# LD_driver.net
KiCad netlist of a schematic drawn in Altium Designer
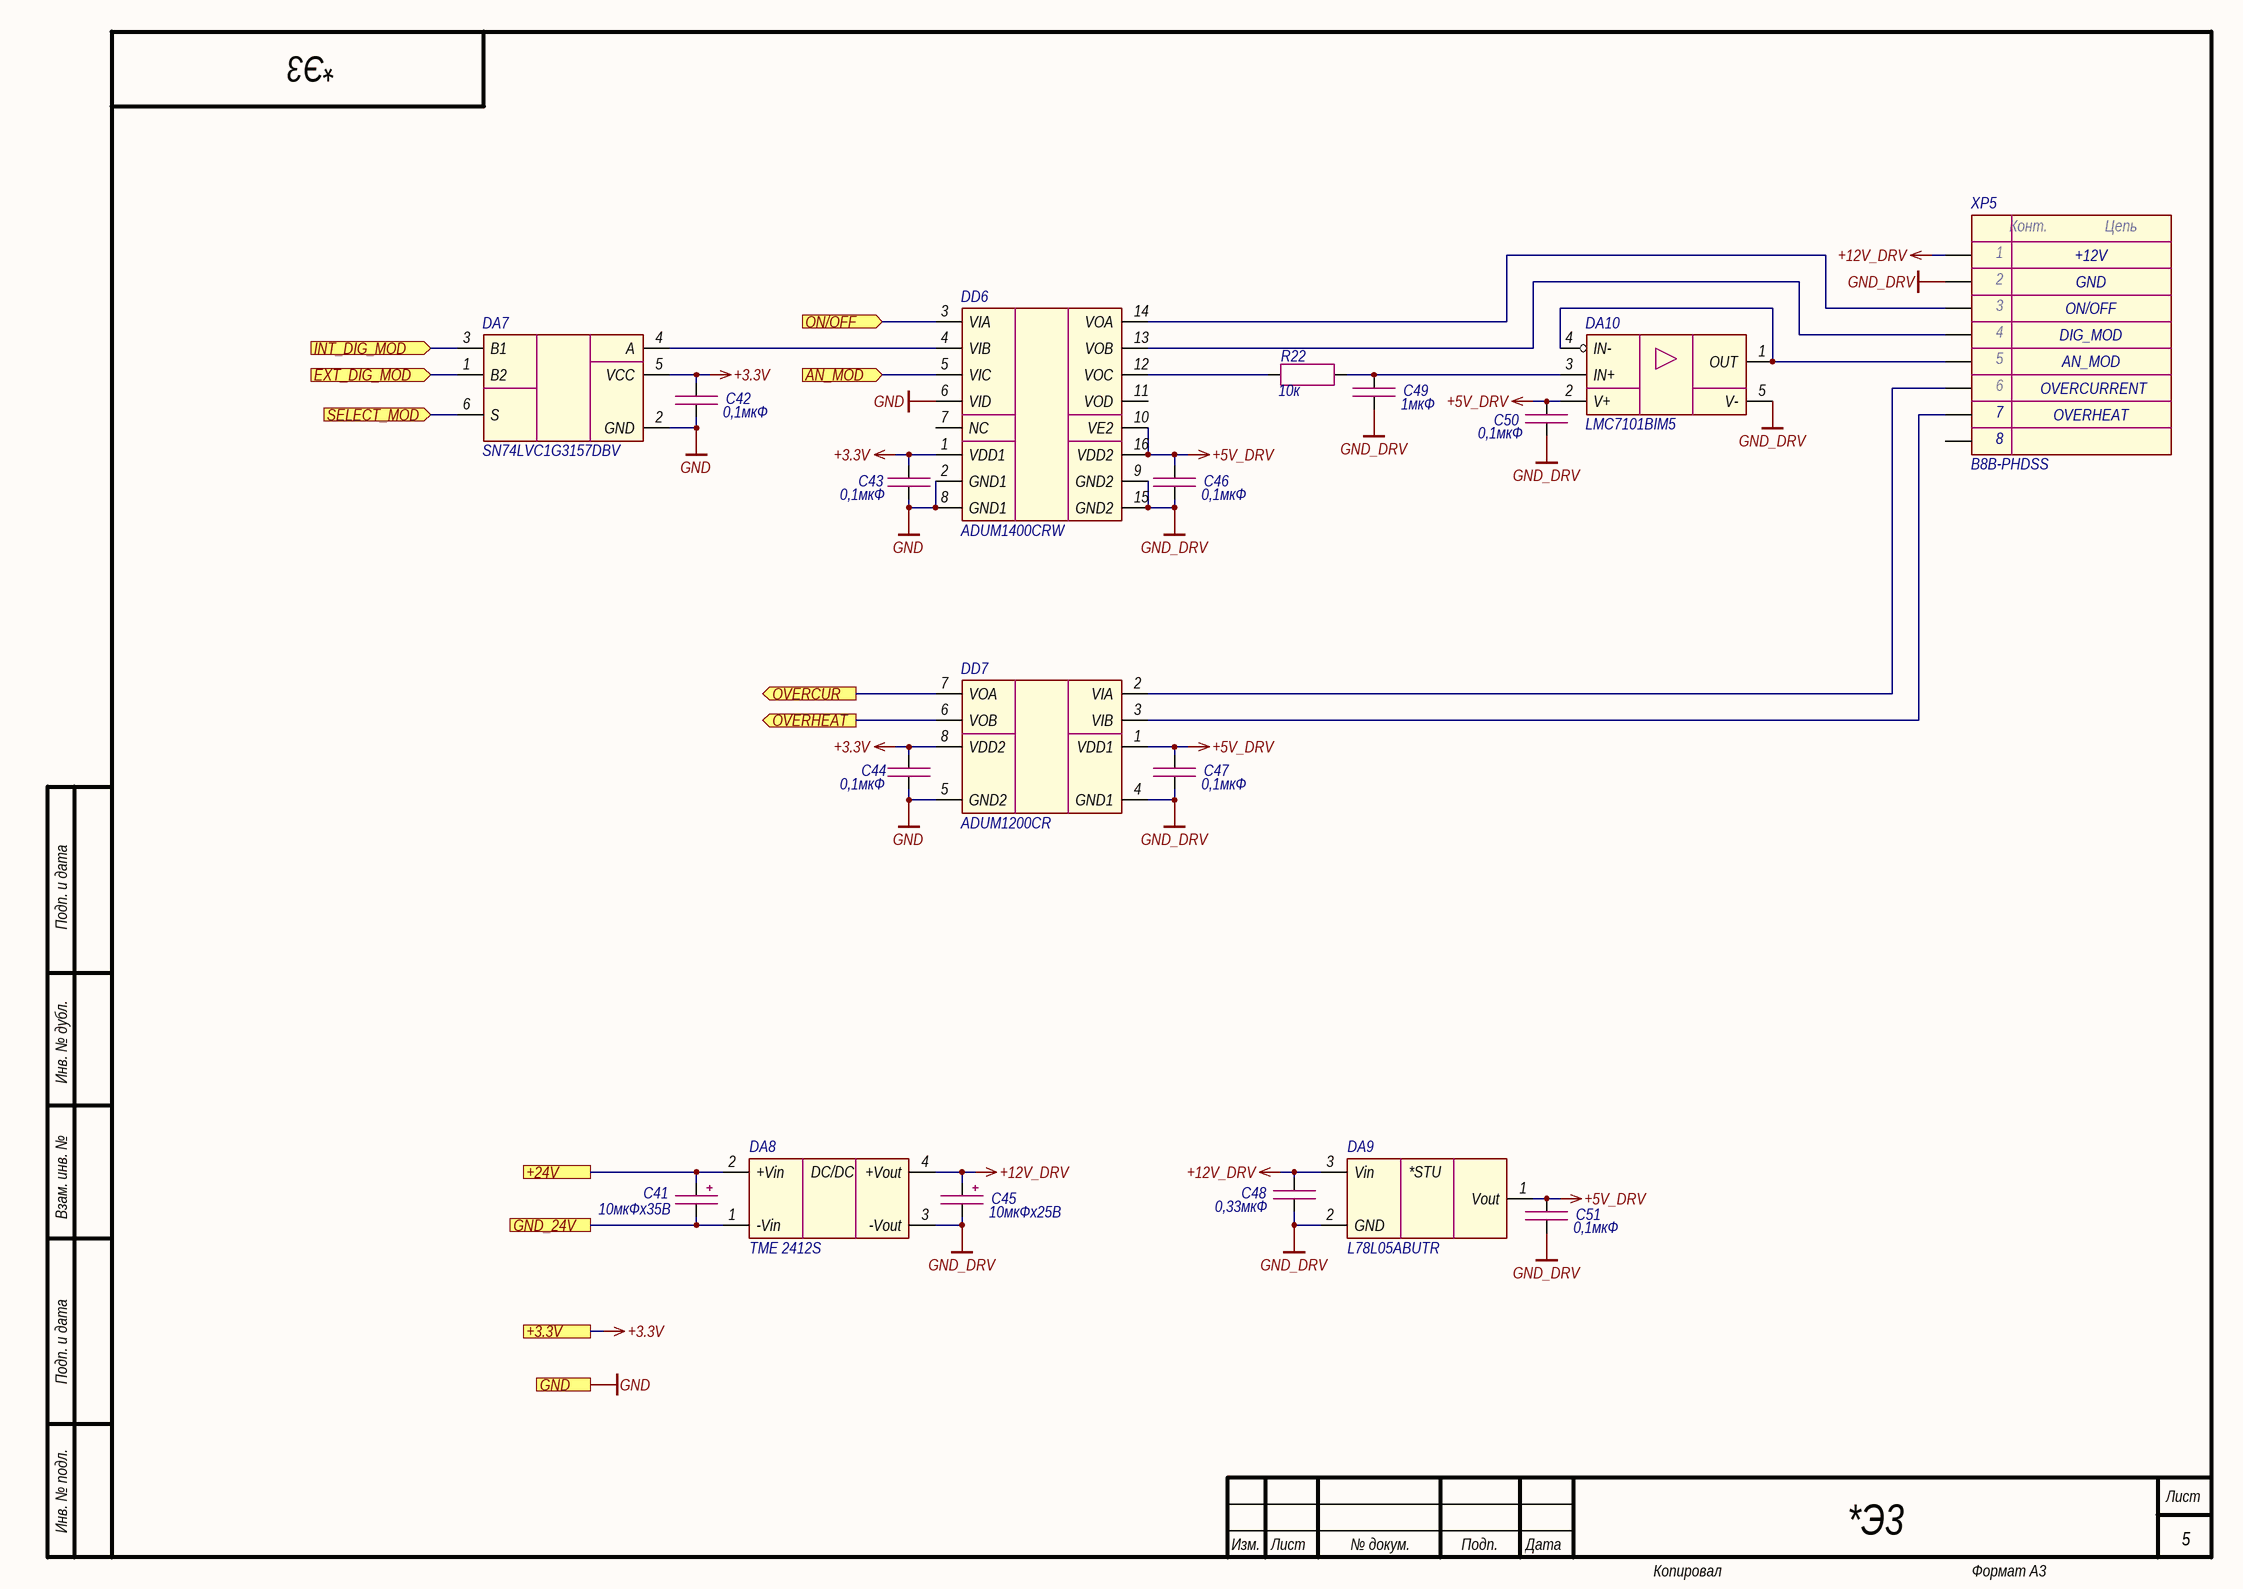
[diagram p0: LD_driver.SchDoc]

(export (version "E")
  (design (tool "Eeschema 10.0.6"))
  (components
    (comp (ref "C41")
      (value "10мкФх35B")
      (footprint "Pcb_library:CAP_C")
      (libsource (lib "Schem_library") (part "Capacitor_Polar"))
    )
    (comp (ref "C42")
      (value "0,1мкФ")
      (footprint "Pcb_library:CAP_0603")
      (fields (field (name "MANUFACTURER") "Murata"))
      (libsource (lib "Schem_library") (part "Capacitor"))
    )
    (comp (ref "C43")
      (value "0,1мкФ")
      (footprint "Pcb_library:CAP_0603")
      (fields (field (name "MANUFACTURER") "Murata"))
      (libsource (lib "Schem_library") (part "Capacitor"))
    )
    (comp (ref "C44")
      (value "0,1мкФ")
      (footprint "Pcb_library:CAP_0603")
      (fields (field (name "MANUFACTURER") "Murata"))
      (libsource (lib "Schem_library") (part "Capacitor"))
    )
    (comp (ref "C45")
      (value "10мкФх25B")
      (footprint "Pcb_library:CAP_B")
      (libsource (lib "Schem_library") (part "Capacitor_Polar"))
    )
    (comp (ref "C46")
      (value "0,1мкФ")
      (footprint "Pcb_library:CAP_0603")
      (fields (field (name "MANUFACTURER") "Murata"))
      (libsource (lib "Schem_library") (part "Capacitor"))
    )
    (comp (ref "C47")
      (value "0,1мкФ")
      (footprint "Pcb_library:CAP_0603")
      (fields (field (name "MANUFACTURER") "Murata"))
      (libsource (lib "Schem_library") (part "Capacitor"))
    )
    (comp (ref "C48")
      (value "0,33мкФ")
      (footprint "Pcb_library:CAP_0805")
      (fields (field (name "MANUFACTURER") "Murata"))
      (libsource (lib "Schem_library") (part "Capacitor"))
    )
    (comp (ref "C49")
      (value "1мкФ")
      (footprint "Pcb_library:CAP_0603")
      (fields (field (name "MANUFACTURER") "Murata"))
      (libsource (lib "Schem_library") (part "Capacitor"))
    )
    (comp (ref "C50")
      (value "0,1мкФ")
      (footprint "Pcb_library:CAP_0603")
      (fields (field (name "MANUFACTURER") "Murata"))
      (libsource (lib "Schem_library") (part "Capacitor"))
    )
    (comp (ref "C51")
      (value "0,1мкФ")
      (footprint "Pcb_library:CAP_0603")
      (fields (field (name "MANUFACTURER") "Murata"))
      (libsource (lib "Schem_library") (part "Capacitor"))
    )
    (comp (ref "DA7")
      (value "SN74LVC1G3157DBV")
      (footprint "Pcb_library:SOT-23-6")
      (fields (field (name "MANUFACTURER") "Texas Instruments"))
      (libsource (lib "Schem_library") (part "SN74LVC1G3157"))
    )
    (comp (ref "DA8")
      (value "TME 2412S")
      (footprint "Pcb_library:TME (SIP-4)")
      (fields (field (name "MANUFACTURER") "Traco Power"))
      (libsource (lib "Schem_library") (part "TME"))
    )
    (comp (ref "DA9")
      (value "L78L05ABUTR")
      (footprint "Pcb_library:SOT-89")
      (fields (field (name "MANUFACTURER") "STMicroelectronics"))
      (libsource (lib "Schem_library") (part "LD2981ABU50TR"))
    )
    (comp (ref "DA10")
      (value "LMC7101BIM5")
      (footprint "Pcb_library:SOT-23-5")
      (fields (field (name "MANUFACTURER") "Texas Instruments"))
      (libsource (lib "Schem_library") (part "LMC7101"))
    )
    (comp (ref "DD6")
      (value "ADUM1400CRW")
      (footprint "Pcb_library:SOIC-16W")
      (fields (field (name "MANUFACTURER") "Analog Devices"))
      (libsource (lib "Schem_library") (part "ADUM1400"))
    )
    (comp (ref "DD7")
      (value "ADUM1200CR")
      (footprint "Pcb_library:SOIC-8")
      (fields (field (name "MANUFACTURER") "Analog Devices"))
      (libsource (lib "Schem_library") (part "ADUM1200"))
    )
    (comp (ref "R22")
      (value "10к")
      (footprint "Pcb_library:RES_0603")
      (fields (field (name "MANUFACTURER") "Yageo"))
      (libsource (lib "Schem_library") (part "Resistor"))
    )
    (comp (ref "XP5")
      (value "B8B-PHDSS")
      (footprint "Pcb_library:B8B-PHDSS")
      (fields (field (name "MANUFACTURER") "JST"))
      (libsource (lib "Schem_library") (part "Connector-8"))
    )
  )
  (nets
    (net (code "1") (name "+3.3V") (class "Default")
      (node (ref "C42") (pin "1") (pinfunction "1_1") (pintype "passive"))
      (node (ref "C43") (pin "1") (pinfunction "1_1") (pintype "passive"))
      (node (ref "C44") (pin "1") (pinfunction "1_1") (pintype "passive"))
      (node (ref "DA7") (pin "5") (pinfunction "VCC_5") (pintype "passive"))
      (node (ref "DD6") (pin "1") (pinfunction "VDD1_1") (pintype "passive"))
      (node (ref "DD7") (pin "8") (pinfunction "VDD2_8") (pintype "passive"))
    )
    (net (code "2") (name "+5V_DRV") (class "Default")
      (node (ref "C46") (pin "1") (pinfunction "1_1") (pintype "passive"))
      (node (ref "C47") (pin "1") (pinfunction "1_1") (pintype "passive"))
      (node (ref "C50") (pin "1") (pinfunction "1_1") (pintype "passive"))
      (node (ref "C51") (pin "1") (pinfunction "1_1") (pintype "passive"))
      (node (ref "DA10") (pin "2") (pinfunction "V+_2") (pintype "passive"))
      (node (ref "DA9") (pin "1") (pinfunction "Vout_1") (pintype "passive"))
      (node (ref "DD6") (pin "10") (pinfunction "VE2_10") (pintype "passive"))
      (node (ref "DD6") (pin "16") (pinfunction "VDD2_16") (pintype "passive"))
      (node (ref "DD7") (pin "1") (pinfunction "VDD1_1") (pintype "passive"))
    )
    (net (code "3") (name "+12V_DRV") (class "Default")
      (node (ref "C45") (pin "1") (pinfunction "1_1") (pintype "passive"))
      (node (ref "C48") (pin "2") (pinfunction "2_2") (pintype "passive"))
      (node (ref "DA8") (pin "4") (pinfunction "+Vout_4") (pintype "passive"))
      (node (ref "DA9") (pin "3") (pinfunction "Vin_3") (pintype "passive"))
      (node (ref "XP5") (pin "1") (pintype "passive"))
    )
    (net (code "4") (name "/+24V") (class "Default")
      (node (ref "C41") (pin "1") (pinfunction "1_1") (pintype "passive"))
      (node (ref "DA8") (pin "2") (pinfunction "+Vin_2") (pintype "passive"))
    )
    (net (code "5") (name "/AN_MOD") (class "Default")
      (node (ref "DD6") (pin "5") (pinfunction "VIC_5") (pintype "passive"))
    )
    (net (code "6") (name "/EXT_DIG_MOD") (class "Default")
      (node (ref "DA7") (pin "1") (pinfunction "B2_1") (pintype "passive"))
    )
    (net (code "7") (name "/GND_24V") (class "Default")
      (node (ref "C41") (pin "2") (pinfunction "2_2") (pintype "passive"))
      (node (ref "DA8") (pin "1") (pinfunction "-Vin_1") (pintype "passive"))
    )
    (net (code "8") (name "/INT_DIG_MOD") (class "Default")
      (node (ref "DA7") (pin "3") (pinfunction "B1_3") (pintype "passive"))
    )
    (net (code "9") (name "/ON{slash}OFF") (class "Default")
      (node (ref "DD6") (pin "3") (pinfunction "VIA_3") (pintype "passive"))
    )
    (net (code "10") (name "/OVERCUR") (class "Default")
      (node (ref "DD7") (pin "7") (pinfunction "VOA_7") (pintype "passive"))
    )
    (net (code "11") (name "/OVERHEAT") (class "Default")
      (node (ref "DD7") (pin "6") (pinfunction "VOB_6") (pintype "passive"))
    )
    (net (code "12") (name "/SELECT_MOD") (class "Default")
      (node (ref "DA7") (pin "6") (pinfunction "S_6") (pintype "passive"))
    )
    (net (code "13") (name "GND") (class "Default")
      (node (ref "C42") (pin "2") (pinfunction "2_2") (pintype "passive"))
      (node (ref "C43") (pin "2") (pinfunction "2_2") (pintype "passive"))
      (node (ref "C44") (pin "2") (pinfunction "2_2") (pintype "passive"))
      (node (ref "DA7") (pin "2") (pinfunction "GND_2") (pintype "passive"))
      (node (ref "DD6") (pin "2") (pinfunction "GND1_2") (pintype "passive"))
      (node (ref "DD6") (pin "6") (pinfunction "VID_6") (pintype "passive"))
      (node (ref "DD6") (pin "8") (pinfunction "GND1_8") (pintype "passive"))
      (node (ref "DD7") (pin "5") (pinfunction "GND2_5") (pintype "passive"))
    )
    (net (code "14") (name "GND_DRV") (class "Default")
      (node (ref "C45") (pin "2") (pinfunction "2_2") (pintype "passive"))
      (node (ref "C46") (pin "2") (pinfunction "2_2") (pintype "passive"))
      (node (ref "C47") (pin "2") (pinfunction "2_2") (pintype "passive"))
      (node (ref "C48") (pin "1") (pinfunction "1_1") (pintype "passive"))
      (node (ref "C49") (pin "2") (pinfunction "2_2") (pintype "passive"))
      (node (ref "C50") (pin "2") (pinfunction "2_2") (pintype "passive"))
      (node (ref "C51") (pin "2") (pinfunction "2_2") (pintype "passive"))
      (node (ref "DA10") (pin "5") (pinfunction "V-_5") (pintype "passive"))
      (node (ref "DA8") (pin "3") (pinfunction "-Vout_3") (pintype "passive"))
      (node (ref "DA9") (pin "2") (pinfunction "GND_2") (pintype "passive"))
      (node (ref "DD6") (pin "15") (pinfunction "GND2_15") (pintype "passive"))
      (node (ref "DD6") (pin "9") (pinfunction "GND2_9") (pintype "passive"))
      (node (ref "DD7") (pin "4") (pinfunction "GND1_4") (pintype "passive"))
      (node (ref "XP5") (pin "2") (pintype "passive"))
    )
    (net (code "15") (name "Net-(DA7-A)") (class "Default")
      (node (ref "DA7") (pin "4") (pinfunction "A_4") (pintype "passive"))
      (node (ref "DD6") (pin "4") (pinfunction "VIB_4") (pintype "passive"))
    )
    (net (code "16") (name "Net-(DA10-IN+)") (class "Default")
      (node (ref "C49") (pin "1") (pinfunction "1_1") (pintype "passive"))
      (node (ref "DA10") (pin "3") (pinfunction "IN+_3") (pintype "passive"))
      (node (ref "R22") (pin "2") (pinfunction "2_2") (pintype "passive"))
    )
    (net (code "17") (name "Net-(DA10-IN-)") (class "Default")
      (node (ref "DA10") (pin "1") (pinfunction "OUT_1") (pintype "passive"))
      (node (ref "DA10") (pin "4") (pinfunction "IN-_4") (pintype "passive"))
      (node (ref "XP5") (pin "5") (pintype "passive"))
    )
    (net (code "18") (name "Net-(DD6-VOA)") (class "Default")
      (node (ref "DD6") (pin "14") (pinfunction "VOA_14") (pintype "passive"))
      (node (ref "XP5") (pin "3") (pintype "passive"))
    )
    (net (code "19") (name "Net-(DD6-VOB)") (class "Default")
      (node (ref "DD6") (pin "13") (pinfunction "VOB_13") (pintype "passive"))
      (node (ref "XP5") (pin "4") (pintype "passive"))
    )
    (net (code "20") (name "Net-(DD6-VOC)") (class "Default")
      (node (ref "DD6") (pin "12") (pinfunction "VOC_12") (pintype "passive"))
      (node (ref "R22") (pin "1") (pinfunction "1_1") (pintype "passive"))
    )
    (net (code "21") (name "Net-(DD7-VIA)") (class "Default")
      (node (ref "DD7") (pin "2") (pinfunction "VIA_2") (pintype "passive"))
      (node (ref "XP5") (pin "6") (pintype "passive"))
    )
    (net (code "22") (name "Net-(DD7-VIB)") (class "Default")
      (node (ref "DD7") (pin "3") (pinfunction "VIB_3") (pintype "passive"))
      (node (ref "XP5") (pin "7") (pintype "passive"))
    )
    (net (code "23") (name "unconnected-(DD6-NC-Pad7)") (class "Default")
      (node (ref "DD6") (pin "7") (pinfunction "NC_7") (pintype "passive"))
    )
    (net (code "24") (name "unconnected-(DD6-VOD-Pad11)") (class "Default")
      (node (ref "DD6") (pin "11") (pinfunction "VOD_11") (pintype "passive"))
    )
    (net (code "25") (name "unconnected-(XP5-Pad8)") (class "Default")
      (node (ref "XP5") (pin "8") (pintype "passive"))
    )
  )
)
